# FM-Radio-Receiver-1_5V.net
KiCad netlist of a schematic drawn in EAGLE
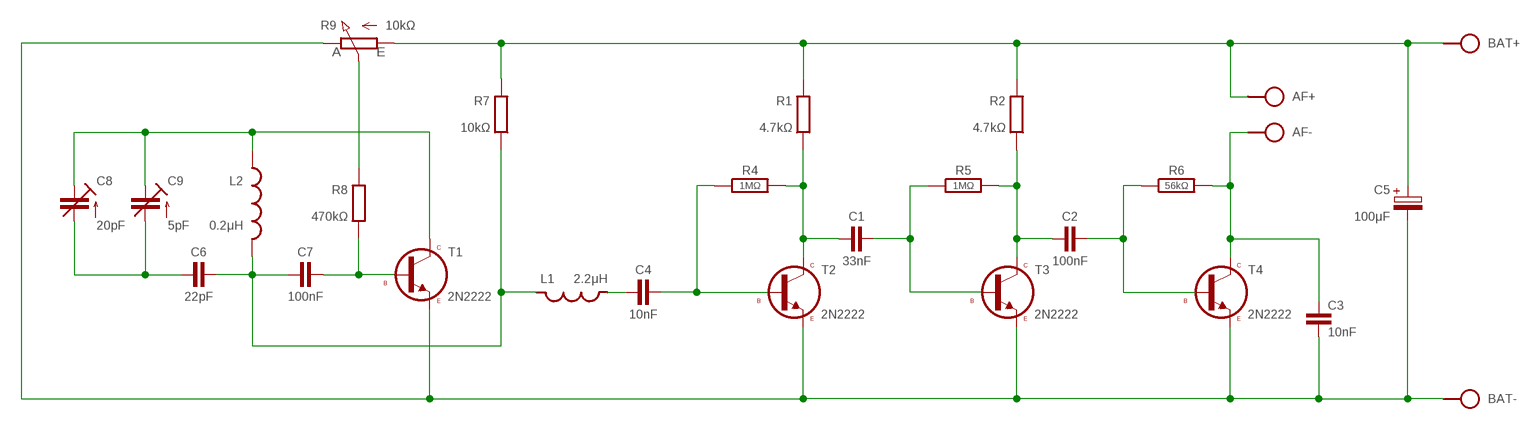
[diagram p0: schematic, sheet 1]

(export (version "E")
  (design (tool "Eeschema 10.0.6"))
  (components
    (comp (ref "AF")
      (value "SPAD+-+-")
      (footprint "eagle-import:SPAD+-")
      (libsource (lib "eagle-import") (part "SPAD+-+-"))
    )
    (comp (ref "BAT")
      (value "SPAD+-+-")
      (footprint "eagle-import:SPAD+-")
      (libsource (lib "eagle-import") (part "SPAD+-+-"))
    )
    (comp (ref "C1")
      (value "33nF")
      (footprint "eagle-import:C050-020X044")
      (libsource (lib "eagle-import") (part "C-H050-020X044"))
    )
    (comp (ref "C2")
      (value "100nF")
      (footprint "eagle-import:C050-020X044")
      (libsource (lib "eagle-import") (part "C-H050-020X044"))
    )
    (comp (ref "C3")
      (value "10nF")
      (footprint "eagle-import:C050-025X060")
      (libsource (lib "eagle-import") (part "C025-025X060"))
    )
    (comp (ref "C4")
      (value "10nF")
      (footprint "eagle-import:C050-020X044")
      (libsource (lib "eagle-import") (part "C-H050-020X044"))
    )
    (comp (ref "C5")
      (value "100μF")
      (footprint "eagle-import:E2.5-4_V")
      (libsource (lib "eagle-import") (part "CPOLE2,5-4/V"))
    )
    (comp (ref "C6")
      (value "22pF")
      (footprint "eagle-import:C050-020X036")
      (libsource (lib "eagle-import") (part "C-H050-020X036"))
    )
    (comp (ref "C7")
      (value "100nF")
      (footprint "eagle-import:C075-020X044")
      (libsource (lib "eagle-import") (part "C-H075-020X044"))
    )
    (comp (ref "C8")
      (value "20pF")
      (footprint "eagle-import:TRIM-2222-808")
      (libsource (lib "eagle-import") (part "C-TR-PH201272222-808-2PIND"))
    )
    (comp (ref "C9")
      (value "5pF")
      (footprint "eagle-import:CTRIMTZ03")
      (libsource (lib "eagle-import") (part "C-TR-PH20127-TZ03"))
    )
    (comp (ref "L1")
      (value "2.2μH")
      (footprint "eagle-import:L-03_10")
      (libsource (lib "eagle-import") (part "L-H-SHORT-03/10"))
    )
    (comp (ref "L2")
      (value "0.2μH")
      (footprint "eagle-import:L-10_10Y")
      (libsource (lib "eagle-import") (part "L10/10Y"))
    )
    (comp (ref "R1")
      (value "4.7kΩ")
      (footprint "eagle-import:0204_10-V")
      (libsource (lib "eagle-import") (part "R0204/10-V"))
    )
    (comp (ref "R2")
      (value "4.7kΩ")
      (footprint "eagle-import:0204_10-V")
      (libsource (lib "eagle-import") (part "R0204/10-V"))
    )
    (comp (ref "R4")
      (value "1MΩ")
      (footprint "eagle-import:0204_10-V")
      (libsource (lib "eagle-import") (part "R-H0204/10-V"))
    )
    (comp (ref "R5")
      (value "1MΩ")
      (footprint "eagle-import:0204_10-V")
      (libsource (lib "eagle-import") (part "R-H0204/10-V"))
    )
    (comp (ref "R6")
      (value "56kΩ")
      (footprint "eagle-import:0204_10-V")
      (libsource (lib "eagle-import") (part "R-H0204/10-V"))
    )
    (comp (ref "R7")
      (value "10kΩ")
      (footprint "eagle-import:0204_10-V")
      (libsource (lib "eagle-import") (part "R0204/10-V"))
    )
    (comp (ref "R8")
      (value "470kΩ")
      (footprint "eagle-import:0204_10-V")
      (libsource (lib "eagle-import") (part "R0204/10-V"))
    )
    (comp (ref "R9")
      (value "10kΩ")
      (footprint "eagle-import:CONN-3P")
      (libsource (lib "eagle-import") (part "POT-H-3P"))
    )
    (comp (ref "T1")
      (value "2N2222")
      (footprint "eagle-import:TO92")
      (libsource (lib "eagle-import") (part "2N2222"))
    )
    (comp (ref "T2")
      (value "2N2222")
      (footprint "eagle-import:TO92")
      (libsource (lib "eagle-import") (part "2N2222"))
    )
    (comp (ref "T3")
      (value "2N2222")
      (footprint "eagle-import:TO92")
      (libsource (lib "eagle-import") (part "2N2222"))
    )
    (comp (ref "T4")
      (value "2N2222")
      (footprint "eagle-import:TO92")
      (libsource (lib "eagle-import") (part "2N2222"))
    )
  )
  (nets
    (net (code "1") (name "Net-(AFA-P$1)") (class "Default")
      (node (ref "AF") (pin "2") (pinfunction "P$1_2") (pintype "passive"))
      (node (ref "BAT") (pin "2") (pinfunction "P$1_2") (pintype "passive"))
      (node (ref "C5") (pin "+") (pinfunction "+_+") (pintype "passive"))
      (node (ref "R1") (pin "1") (pinfunction "2_1") (pintype "passive"))
      (node (ref "R2") (pin "1") (pinfunction "2_1") (pintype "passive"))
      (node (ref "R7") (pin "1") (pinfunction "2_1") (pintype "passive"))
      (node (ref "R9") (pin "1") (pinfunction "A_1") (pintype "passive"))
    )
    (net (code "2") (name "Net-(AFB-P$1)") (class "Default")
      (node (ref "AF") (pin "1") (pinfunction "P$1_1") (pintype "passive"))
      (node (ref "C3") (pin "1") (pinfunction "1_1") (pintype "passive"))
      (node (ref "R6") (pin "2") (pinfunction "2_2") (pintype "passive"))
      (node (ref "T4") (pin "3") (pinfunction "C_3") (pintype "passive"))
    )
    (net (code "3") (name "Net-(BATB-P$1)") (class "Default")
      (node (ref "BAT") (pin "1") (pinfunction "P$1_1") (pintype "passive"))
      (node (ref "C3") (pin "2") (pinfunction "2_2") (pintype "passive"))
      (node (ref "C5") (pin "-") (pinfunction "-_-") (pintype "passive"))
      (node (ref "R9") (pin "3") (pinfunction "E_3") (pintype "passive"))
      (node (ref "T1") (pin "1") (pinfunction "E_1") (pintype "passive"))
      (node (ref "T2") (pin "1") (pinfunction "E_1") (pintype "passive"))
      (node (ref "T3") (pin "1") (pinfunction "E_1") (pintype "passive"))
      (node (ref "T4") (pin "1") (pinfunction "E_1") (pintype "passive"))
    )
    (net (code "4") (name "Net-(C4-Pad1)") (class "Default")
      (node (ref "C4") (pin "1") (pinfunction "1_1") (pintype "passive"))
      (node (ref "L1") (pin "1") (pinfunction "1_1") (pintype "passive"))
    )
    (net (code "5") (name "Net-(C8-A)") (class "Default")
      (node (ref "C6") (pin "1") (pinfunction "1_1") (pintype "passive"))
      (node (ref "C8") (pin "2") (pinfunction "A_2") (pintype "passive"))
      (node (ref "C9") (pin "1") (pinfunction "A_1") (pintype "passive"))
    )
    (net (code "6") (name "Net-(C8-E)") (class "Default")
      (node (ref "C8") (pin "3") (pinfunction "E_3") (pintype "passive"))
      (node (ref "C9") (pin "2") (pinfunction "E_2") (pintype "passive"))
      (node (ref "L2") (pin "P$1") (pinfunction "1_P$1") (pintype "passive"))
      (node (ref "T1") (pin "3") (pinfunction "C_3") (pintype "passive"))
    )
    (net (code "7") (name "Net-(L2-2)") (class "Default")
      (node (ref "C6") (pin "2") (pinfunction "2_2") (pintype "passive"))
      (node (ref "C7") (pin "1") (pinfunction "1_1") (pintype "passive"))
      (node (ref "L1") (pin "2") (pinfunction "2_2") (pintype "passive"))
      (node (ref "L2") (pin "P$2") (pinfunction "2_P$2") (pintype "passive"))
      (node (ref "R7") (pin "2") (pinfunction "1_2") (pintype "passive"))
    )
    (net (code "8") (name "Net-(R1-1)") (class "Default")
      (node (ref "C1") (pin "1") (pinfunction "1_1") (pintype "passive"))
      (node (ref "R1") (pin "2") (pinfunction "1_2") (pintype "passive"))
      (node (ref "R4") (pin "2") (pinfunction "2_2") (pintype "passive"))
      (node (ref "T2") (pin "3") (pinfunction "C_3") (pintype "passive"))
    )
    (net (code "9") (name "Net-(R2-1)") (class "Default")
      (node (ref "C2") (pin "1") (pinfunction "1_1") (pintype "passive"))
      (node (ref "R2") (pin "2") (pinfunction "1_2") (pintype "passive"))
      (node (ref "R5") (pin "2") (pinfunction "2_2") (pintype "passive"))
      (node (ref "T3") (pin "3") (pinfunction "C_3") (pintype "passive"))
    )
    (net (code "10") (name "Net-(R8-1)") (class "Default")
      (node (ref "C7") (pin "2") (pinfunction "2_2") (pintype "passive"))
      (node (ref "R8") (pin "2") (pinfunction "1_2") (pintype "passive"))
      (node (ref "T1") (pin "2") (pinfunction "B_2") (pintype "passive"))
    )
    (net (code "11") (name "Net-(R8-2)") (class "Default")
      (node (ref "R8") (pin "1") (pinfunction "2_1") (pintype "passive"))
      (node (ref "R9") (pin "2") (pinfunction "S_2") (pintype "passive"))
    )
    (net (code "12") (name "Net-(T2-B)") (class "Default")
      (node (ref "C4") (pin "2") (pinfunction "2_2") (pintype "passive"))
      (node (ref "R4") (pin "1") (pinfunction "1_1") (pintype "passive"))
      (node (ref "T2") (pin "2") (pinfunction "B_2") (pintype "passive"))
    )
    (net (code "13") (name "Net-(T3-B)") (class "Default")
      (node (ref "C1") (pin "2") (pinfunction "2_2") (pintype "passive"))
      (node (ref "R5") (pin "1") (pinfunction "1_1") (pintype "passive"))
      (node (ref "T3") (pin "2") (pinfunction "B_2") (pintype "passive"))
    )
    (net (code "14") (name "Net-(T4-B)") (class "Default")
      (node (ref "C2") (pin "2") (pinfunction "2_2") (pintype "passive"))
      (node (ref "R6") (pin "1") (pinfunction "1_1") (pintype "passive"))
      (node (ref "T4") (pin "2") (pinfunction "B_2") (pintype "passive"))
    )
  )
)
